# WIFI_Module.net
KiCad netlist of a schematic drawn in Altium Designer
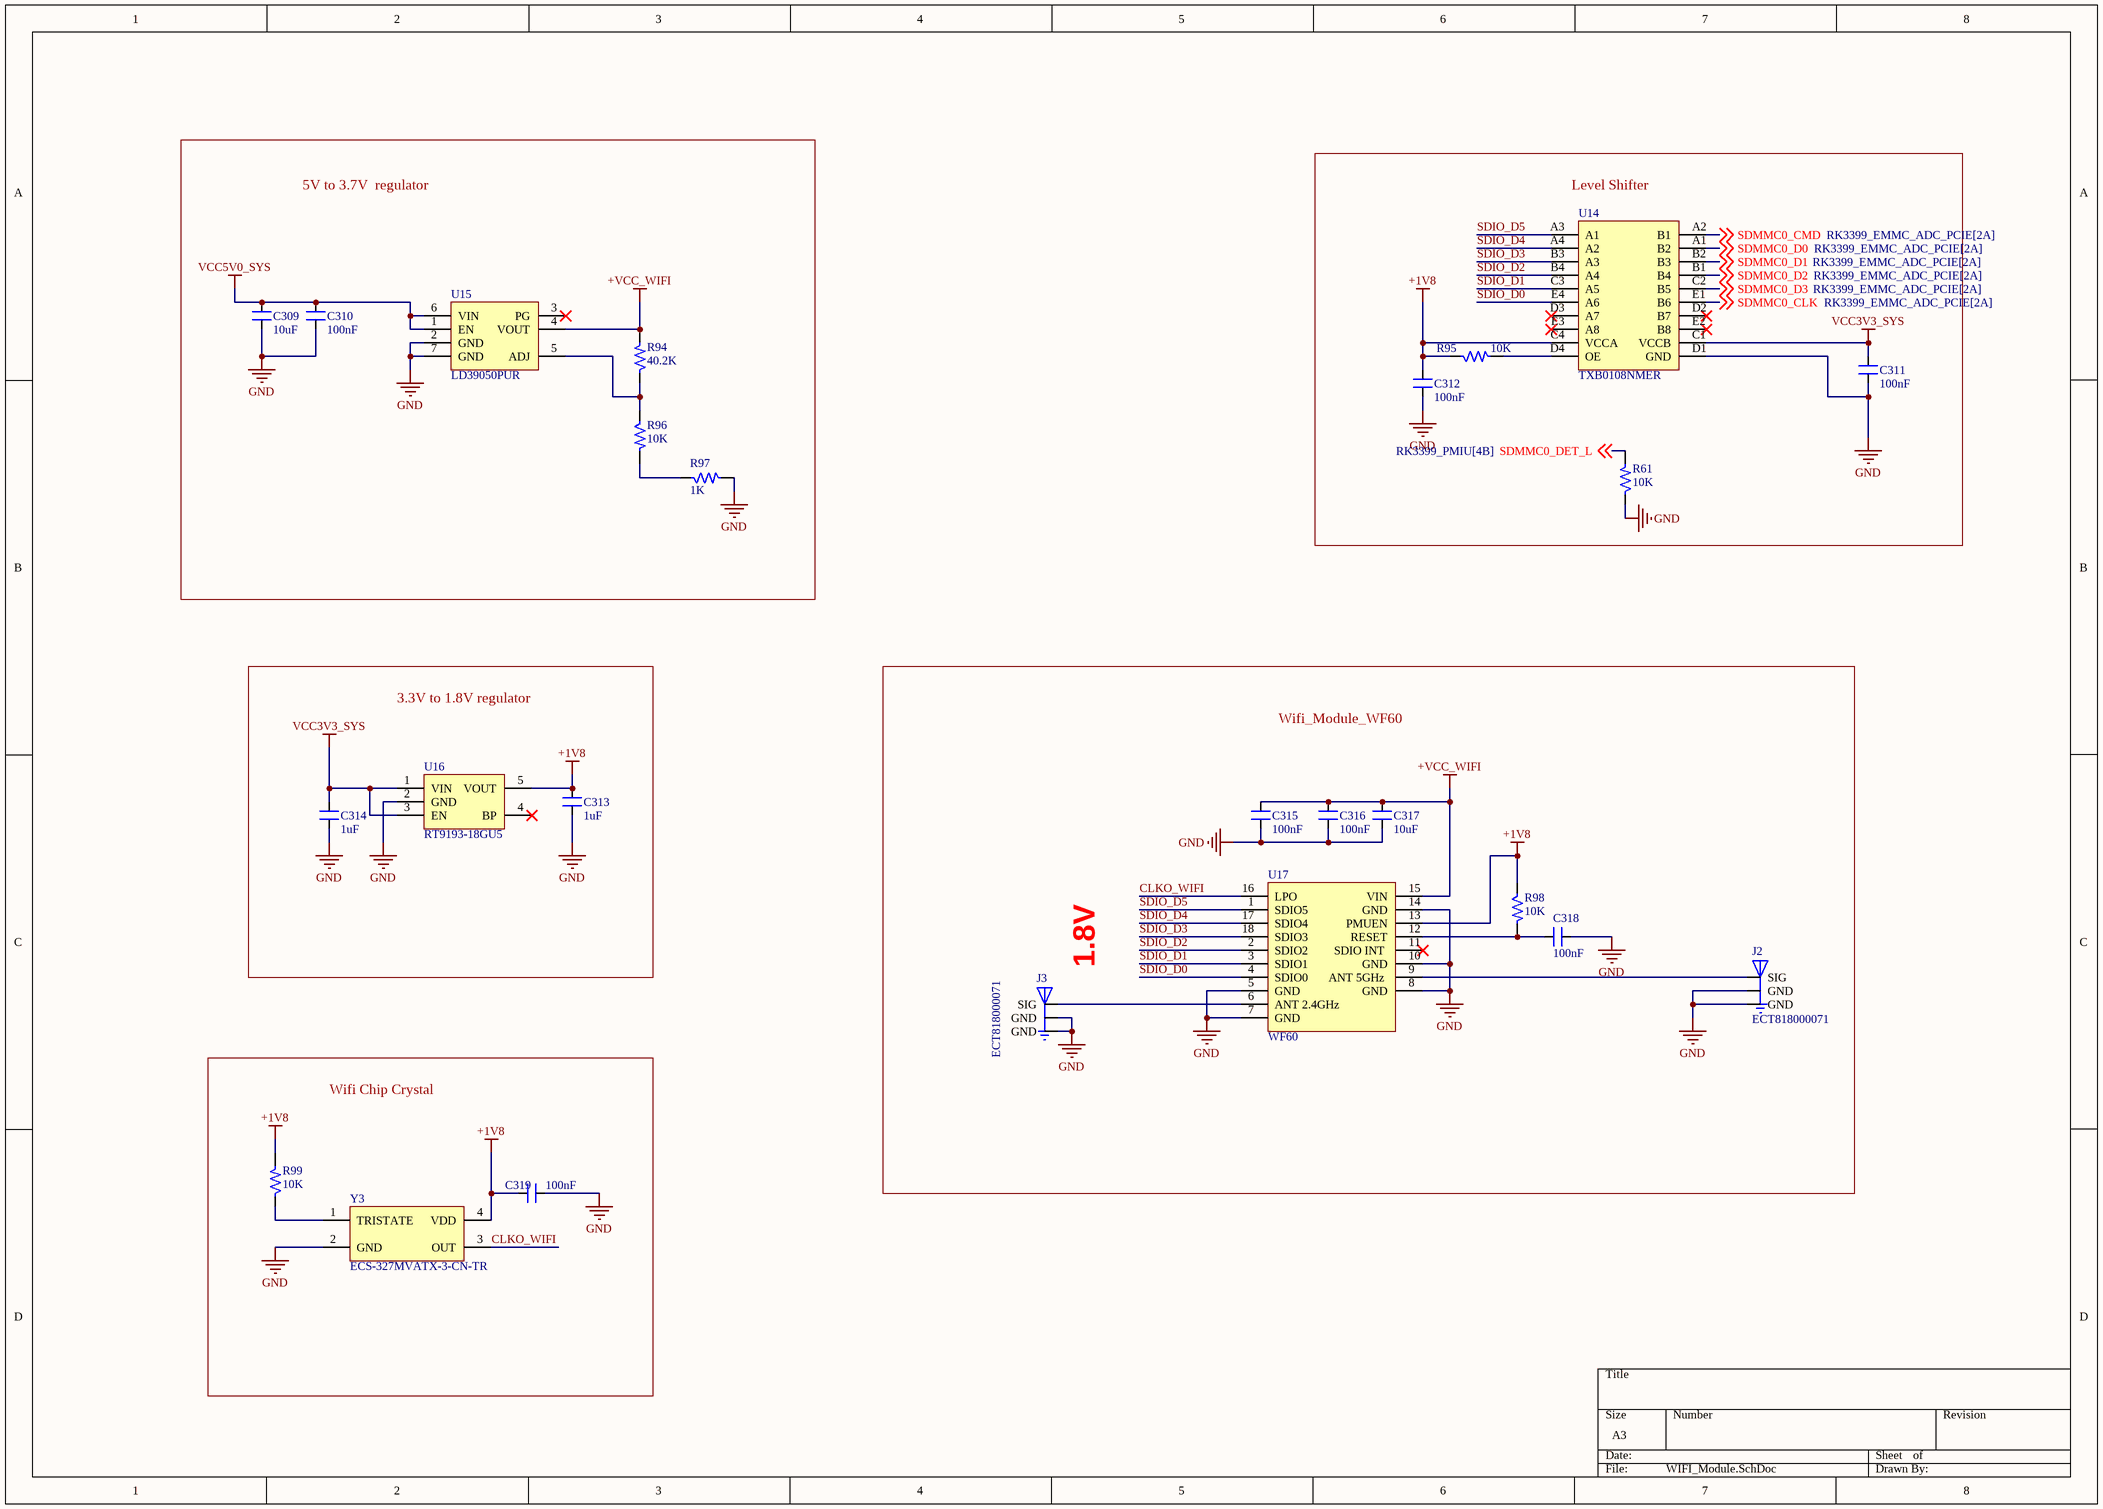
[diagram p0: WIFI_Module.SchDoc]

(export (version "E")
  (design (tool "Eeschema 10.0.6"))
  (components
    (comp (ref "C309")
      (value "10uF")
      (footprint "CAP_0603")
      (description "10µF ±10% 10V Ceramic Capacitor X5R 0603 (1608 Metric)")
      (fields
        (field (name "MANUFACTURER PART NUMBER") "GRM188R61A106KE69J")
        (field (name "MANUFACTURER") "Murata Electronics")
      )
      (libsource (lib "EsteemPCB_SOM_Course_schlib") (part "CAP_10uF-10V-10%-0603"))
    )
    (comp (ref "C310")
      (value "100nF")
      (footprint "CAP_0201")
      (description "0.1µF ±10% 25V Ceramic Capacitor X5R 0201 (0603 Metric)")
      (fields
        (field (name "MANUFACTURER") "TDK Corporation")
        (field (name "MANUFACTURER PART NUMBER") "C0603X5R1E104K030BB")
      )
      (libsource (lib "EsteemPCB_SOM_Course_schlib") (part "CAP_100nF-25V-10%-0201"))
    )
    (comp (ref "C311")
      (value "100nF")
      (footprint "CAP_0201")
      (description "0.1µF ±10% 25V Ceramic Capacitor X5R 0201 (0603 Metric)")
      (fields
        (field (name "MANUFACTURER") "TDK Corporation")
        (field (name "MANUFACTURER PART NUMBER") "C0603X5R1E104K030BB")
      )
      (libsource (lib "EsteemPCB_SOM_Course_schlib") (part "CAP_100nF-25V-10%-0201"))
    )
    (comp (ref "C312")
      (value "100nF")
      (footprint "CAP_0201")
      (description "0.1µF ±10% 25V Ceramic Capacitor X5R 0201 (0603 Metric)")
      (fields
        (field (name "MANUFACTURER") "TDK Corporation")
        (field (name "MANUFACTURER PART NUMBER") "C0603X5R1E104K030BB")
      )
      (libsource (lib "EsteemPCB_SOM_Course_schlib") (part "CAP_100nF-25V-10%-0201"))
    )
    (comp (ref "C313")
      (value "1uF")
      (footprint "CAP_0201")
      (description "1µF ±20% 16V Ceramic Capacitor X5R 0201 (0603 Metric)")
      (fields
        (field (name "MANUFACTURER") "Samsung Electro-Mechanics")
        (field (name "MANUFACTURER PART NUMBER") "CL03A105MO3NRNH")
      )
      (libsource (lib "EsteemPCB_SOM_Course_schlib") (part "CAP_1uF-16V-10%-0201"))
    )
    (comp (ref "C314")
      (value "1uF")
      (footprint "CAP_0201")
      (description "1µF ±20% 16V Ceramic Capacitor X5R 0201 (0603 Metric)")
      (fields
        (field (name "MANUFACTURER") "Samsung Electro-Mechanics")
        (field (name "MANUFACTURER PART NUMBER") "CL03A105MO3NRNH")
      )
      (libsource (lib "EsteemPCB_SOM_Course_schlib") (part "CAP_1uF-16V-10%-0201"))
    )
    (comp (ref "C315")
      (value "100nF")
      (footprint "CAP_0201")
      (description "0.1µF ±10% 25V Ceramic Capacitor X5R 0201 (0603 Metric)")
      (fields
        (field (name "MANUFACTURER") "TDK Corporation")
        (field (name "MANUFACTURER PART NUMBER") "C0603X5R1E104K030BB")
      )
      (libsource (lib "EsteemPCB_SOM_Course_schlib") (part "CAP_100nF-25V-10%-0201"))
    )
    (comp (ref "C316")
      (value "100nF")
      (footprint "CAP_0201")
      (description "0.1µF ±10% 25V Ceramic Capacitor X5R 0201 (0603 Metric)")
      (fields
        (field (name "MANUFACTURER") "TDK Corporation")
        (field (name "MANUFACTURER PART NUMBER") "C0603X5R1E104K030BB")
      )
      (libsource (lib "EsteemPCB_SOM_Course_schlib") (part "CAP_100nF-25V-10%-0201"))
    )
    (comp (ref "C317")
      (value "10uF")
      (footprint "CAP_0603")
      (description "10µF ±10% 10V Ceramic Capacitor X5R 0603 (1608 Metric)")
      (fields
        (field (name "MANUFACTURER PART NUMBER") "GRM188R61A106KE69J")
        (field (name "MANUFACTURER") "Murata Electronics")
      )
      (libsource (lib "EsteemPCB_SOM_Course_schlib") (part "CAP_10uF-10V-10%-0603"))
    )
    (comp (ref "C318")
      (value "100nF")
      (footprint "CAP_0201")
      (description "0.1µF ±10% 25V Ceramic Capacitor X5R 0201 (0603 Metric)")
      (fields
        (field (name "MANUFACTURER") "TDK Corporation")
        (field (name "MANUFACTURER PART NUMBER") "C0603X5R1E104K030BB")
      )
      (libsource (lib "EsteemPCB_SOM_Course_schlib") (part "CAP_100nF-25V-10%-0201"))
    )
    (comp (ref "C319")
      (value "100nF")
      (footprint "CAP_0201")
      (description "0.1µF ±10% 25V Ceramic Capacitor X5R 0201 (0603 Metric)")
      (fields
        (field (name "MANUFACTURER") "TDK Corporation")
        (field (name "MANUFACTURER PART NUMBER") "C0603X5R1E104K030BB")
      )
      (libsource (lib "EsteemPCB_SOM_Course_schlib") (part "CAP_100nF-25V-10%-0201"))
    )
    (comp (ref "J2")
      (value "ECT818000071")
      (footprint "CON3_UFL_116_SMD_ST")
      (description "SMD RF Connectors/Coaxial Connectors RoHS")
      (fields (field (name "MANUFACTURER") "ECT"))
      (libsource (lib "EsteemPCB_SOM_Course_schlib") (part "CON-PLG_3X1-ECT818000071-ST-SMD"))
    )
    (comp (ref "J3")
      (value "ECT818000071")
      (footprint "CON3_UFL_116_SMD_ST")
      (description "SMD RF Connectors/Coaxial Connectors RoHS")
      (fields (field (name "MANUFACTURER") "ECT"))
      (libsource (lib "EsteemPCB_SOM_Course_schlib") (part "CON-PLG_3X1-ECT818000071-ST-SMD"))
    )
    (comp (ref "R61")
      (value "10K")
      (footprint "RES_0201")
      (description "10 kOhms ±1% 0.05W, 1/20W Chip Resistor 0201 (0603 Metric) Thick Film")
      (fields
        (field (name "MANUFACTURER") "Stackpole Electronics Inc")
        (field (name "MANUFACTURER PART NUMBER") "RMCF0201FT10K0")
      )
      (libsource (lib "EsteemPCB_SOM_Course_schlib") (part "RES_10K-0.05W-1%-0201"))
    )
    (comp (ref "R94")
      (value "40.2K")
      (footprint "RES_0201")
      (fields
        (field (name "MANUFACTURER") "Yageo")
        (field (name "MANUFACTURER PART NUMBER") "AC0201FR-0740K2L")
      )
      (libsource (lib "EsteemPCB_SOM_Course_schlib") (part "RES_40.2K-0.05W-1%-0201"))
    )
    (comp (ref "R95")
      (value "10K")
      (footprint "RES_0201")
      (description "10 kOhms ±1% 0.05W, 1/20W Chip Resistor 0201 (0603 Metric) Thick Film")
      (fields
        (field (name "MANUFACTURER") "Stackpole Electronics Inc")
        (field (name "MANUFACTURER PART NUMBER") "RMCF0201FT10K0")
      )
      (libsource (lib "EsteemPCB_SOM_Course_schlib") (part "RES_10K-0.05W-1%-0201"))
    )
    (comp (ref "R96")
      (value "10K")
      (footprint "RES_0201")
      (description "10 kOhms ±1% 0.05W, 1/20W Chip Resistor 0201 (0603 Metric) Thick Film")
      (fields
        (field (name "MANUFACTURER") "Stackpole Electronics Inc")
        (field (name "MANUFACTURER PART NUMBER") "RMCF0201FT10K0")
      )
      (libsource (lib "EsteemPCB_SOM_Course_schlib") (part "RES_10K-0.05W-1%-0201"))
    )
    (comp (ref "R97")
      (value "1K")
      (footprint "RES_0201")
      (description "1 kOhms ±1% 0.05W, 1/20W Chip Resistor 0201 (0603 Metric) Thick Film")
      (fields
        (field (name "MANUFACTURER") "Yageo")
        (field (name "MANUFACTURER PART NUMBER") "RC0201FR-071KL")
      )
      (libsource (lib "EsteemPCB_SOM_Course_schlib") (part "RES_1K-0.05W-1%-0201"))
    )
    (comp (ref "R98")
      (value "10K")
      (footprint "RES_0201")
      (description "10 kOhms ±1% 0.05W, 1/20W Chip Resistor 0201 (0603 Metric) Thick Film")
      (fields
        (field (name "MANUFACTURER") "Stackpole Electronics Inc")
        (field (name "MANUFACTURER PART NUMBER") "RMCF0201FT10K0")
      )
      (libsource (lib "EsteemPCB_SOM_Course_schlib") (part "RES_10K-0.05W-1%-0201"))
    )
    (comp (ref "R99")
      (value "10K")
      (footprint "RES_0201")
      (description "10 kOhms ±1% 0.05W, 1/20W Chip Resistor 0201 (0603 Metric) Thick Film")
      (fields
        (field (name "MANUFACTURER") "Stackpole Electronics Inc")
        (field (name "MANUFACTURER PART NUMBER") "RMCF0201FT10K0")
      )
      (libsource (lib "EsteemPCB_SOM_Course_schlib") (part "RES_10K-0.05W-1%-0201"))
    )
    (comp (ref "U14")
      (value "TXB0108NMER")
      (footprint "NFBGA_31.4_125.9X102.36")
      (fields (field (name "MANUFACTURER") "Texas Instruments"))
      (libsource (lib "EsteemPCB_SOM_Course_schlib") (part "IC_TXB0108NMER"))
    )
    (comp (ref "U15")
      (value "LD39050PUR")
      (footprint "DFN-6_37.4_165_33X15_SMD")
      (description "Adjustable 5.5V 0.8V 500mA DFN-6 Linear Voltage Regulators RoHS")
      (fields (field (name "MANUFACTURER") "STMicroelectronics"))
      (libsource (lib "EsteemPCB_SOM_Course_schlib") (part "REG_5.5V-0~5.1V-0.5A-2.55W-DFN-6"))
    )
    (comp (ref "U16")
      (value "RT9193-18GU5")
      (footprint "SC70-5")
      (description "Linear Voltage Regulator IC 1 Output 300mA SC-70-5")
      (fields (field (name "MANUFACTURER") "Richtek USA Inc."))
      (libsource (lib "EsteemPCB_SOM_Course_schlib") (part "REG_1.8V-300mA-5.5V-SC70-5"))
    )
    (comp (ref "U17")
      (value "WF60")
      (footprint "MOD_WF60")
      (description "Amp’ed RF Tech presents the WF60 WiFi dual\r\nband module: 802.11abgn.")
      (fields (field (name "MANUFACTURER") "Amp’ed"))
      (libsource (lib "EsteemPCB_SOM_Course_schlib") (part "MOD_WF60-SMD"))
    )
    (comp (ref "Y3")
      (value "ECS-327MVATX-3-CN-TR")
      (footprint "XTAL_57_35X31_SMD")
      (description "32.768kHz XO (Standard) CMOS Oscillator 1.6V ~ 3.6V Enable/Disable 4-SMD, No Lead")
      (fields (field (name "MANUFACTURER") "ECS INC"))
      (libsource (lib "EsteemPCB_SOM_Course_schlib") (part "XTAL_ECS-327MVATX-2-CN-TR"))
    )
  )
  (nets
    (net (code "1") (name "+1V8") (class "Default")
      (node (ref "C312") (pin "1") (pinfunction "1_1") (pintype "passive"))
      (node (ref "C313") (pin "2") (pinfunction "2_2") (pintype "passive"))
      (node (ref "C319") (pin "1") (pinfunction "1_1") (pintype "passive"))
      (node (ref "R95") (pin "1") (pinfunction "1_1") (pintype "passive"))
      (node (ref "R98") (pin "1") (pinfunction "1_1") (pintype "passive"))
      (node (ref "R99") (pin "2") (pinfunction "2_2") (pintype "passive"))
      (node (ref "U14") (pin "C4") (pinfunction "VCCA_C4") (pintype "passive"))
      (node (ref "U16") (pin "5") (pinfunction "VOUT_5") (pintype "passive"))
      (node (ref "U17") (pin "13") (pinfunction "PMUEN_13") (pintype "passive"))
      (node (ref "Y3") (pin "4") (pinfunction "VDD_4") (pintype "passive"))
    )
    (net (code "2") (name "+VCC_WIFI") (class "Default")
      (node (ref "C315") (pin "1") (pinfunction "1_1") (pintype "passive"))
      (node (ref "C316") (pin "1") (pinfunction "1_1") (pintype "passive"))
      (node (ref "C317") (pin "2") (pinfunction "2_2") (pintype "passive"))
      (node (ref "R94") (pin "2") (pinfunction "2_2") (pintype "passive"))
      (node (ref "U15") (pin "4") (pinfunction "VOUT_4") (pintype "passive"))
      (node (ref "U17") (pin "15") (pinfunction "VIN_15") (pintype "passive"))
    )
    (net (code "3") (name "/CLKO_WIFI") (class "Default")
      (node (ref "U17") (pin "16") (pinfunction "LPO_16") (pintype "passive"))
      (node (ref "Y3") (pin "3") (pinfunction "OUT_3") (pintype "passive"))
    )
    (net (code "4") (name "/SDIO_D0") (class "Default")
      (node (ref "U14") (pin "E4") (pinfunction "A6_E4") (pintype "passive"))
      (node (ref "U17") (pin "4") (pinfunction "SDIO0_4") (pintype "passive"))
    )
    (net (code "5") (name "/SDIO_D1") (class "Default")
      (node (ref "U14") (pin "C3") (pinfunction "A5_C3") (pintype "passive"))
      (node (ref "U17") (pin "3") (pinfunction "SDIO1_3") (pintype "passive"))
    )
    (net (code "6") (name "/SDIO_D2") (class "Default")
      (node (ref "U14") (pin "B4") (pinfunction "A4_B4") (pintype "passive"))
      (node (ref "U17") (pin "2") (pinfunction "SDIO2_2") (pintype "passive"))
    )
    (net (code "7") (name "/SDIO_D3") (class "Default")
      (node (ref "U14") (pin "B3") (pinfunction "A3_B3") (pintype "passive"))
      (node (ref "U17") (pin "18") (pinfunction "SDIO3_18") (pintype "passive"))
    )
    (net (code "8") (name "/SDIO_D4") (class "Default")
      (node (ref "U14") (pin "A4") (pinfunction "A2_A4") (pintype "passive"))
      (node (ref "U17") (pin "17") (pinfunction "SDIO4_17") (pintype "passive"))
    )
    (net (code "9") (name "/SDIO_D5") (class "Default")
      (node (ref "U14") (pin "A3") (pinfunction "A1_A3") (pintype "passive"))
      (node (ref "U17") (pin "1") (pinfunction "SDIO5_1") (pintype "passive"))
    )
    (net (code "10") (name "GND") (class "Default")
      (node (ref "C309") (pin "1") (pinfunction "1_1") (pintype "passive"))
      (node (ref "C310") (pin "2") (pinfunction "2_2") (pintype "passive"))
      (node (ref "C311") (pin "2") (pinfunction "2_2") (pintype "passive"))
      (node (ref "C312") (pin "2") (pinfunction "2_2") (pintype "passive"))
      (node (ref "C313") (pin "1") (pinfunction "1_1") (pintype "passive"))
      (node (ref "C314") (pin "1") (pinfunction "1_1") (pintype "passive"))
      (node (ref "C315") (pin "2") (pinfunction "2_2") (pintype "passive"))
      (node (ref "C316") (pin "2") (pinfunction "2_2") (pintype "passive"))
      (node (ref "C317") (pin "1") (pinfunction "1_1") (pintype "passive"))
      (node (ref "C318") (pin "2") (pinfunction "2_2") (pintype "passive"))
      (node (ref "C319") (pin "2") (pinfunction "2_2") (pintype "passive"))
      (node (ref "J2") (pin "1") (pinfunction "GND_1") (pintype "passive"))
      (node (ref "J2") (pin "3") (pinfunction "GND_3") (pintype "passive"))
      (node (ref "J3") (pin "1") (pinfunction "GND_1") (pintype "passive"))
      (node (ref "J3") (pin "3") (pinfunction "GND_3") (pintype "passive"))
      (node (ref "R61") (pin "1") (pinfunction "1_1") (pintype "passive"))
      (node (ref "R97") (pin "2") (pinfunction "2_2") (pintype "passive"))
      (node (ref "U14") (pin "D1") (pinfunction "GND_D1") (pintype "passive"))
      (node (ref "U15") (pin "2") (pinfunction "GND_2") (pintype "passive"))
      (node (ref "U15") (pin "7") (pinfunction "GND_7") (pintype "passive"))
      (node (ref "U16") (pin "2") (pinfunction "GND_2") (pintype "passive"))
      (node (ref "U17") (pin "10") (pinfunction "GND_10") (pintype "passive"))
      (node (ref "U17") (pin "14") (pinfunction "GND_14") (pintype "passive"))
      (node (ref "U17") (pin "5") (pinfunction "GND_5") (pintype "passive"))
      (node (ref "U17") (pin "7") (pinfunction "GND_7") (pintype "passive"))
      (node (ref "U17") (pin "8") (pinfunction "GND_8") (pintype "passive"))
      (node (ref "Y3") (pin "2") (pinfunction "GND_2") (pintype "passive"))
    )
    (net (code "11") (name "Net-(J2-SIG)") (class "Default")
      (node (ref "J2") (pin "2") (pinfunction "SIG_2") (pintype "passive"))
      (node (ref "U17") (pin "9") (pinfunction "ANT_5GHz_9") (pintype "passive"))
    )
    (net (code "12") (name "Net-(J3-SIG)") (class "Default")
      (node (ref "J3") (pin "2") (pinfunction "SIG_2") (pintype "passive"))
      (node (ref "U17") (pin "6") (pinfunction "ANT_2.4GHz_6") (pintype "passive"))
    )
    (net (code "13") (name "Net-(R96-Pad2)") (class "Default")
      (node (ref "R96") (pin "2") (pinfunction "2_2") (pintype "passive"))
      (node (ref "R97") (pin "1") (pinfunction "1_1") (pintype "passive"))
    )
    (net (code "14") (name "Net-(U14-OE)") (class "Default")
      (node (ref "R95") (pin "2") (pinfunction "2_2") (pintype "passive"))
      (node (ref "U14") (pin "D4") (pinfunction "OE_D4") (pintype "passive"))
    )
    (net (code "15") (name "Net-(U15-ADJ)") (class "Default")
      (node (ref "R94") (pin "1") (pinfunction "1_1") (pintype "passive"))
      (node (ref "R96") (pin "1") (pinfunction "1_1") (pintype "passive"))
      (node (ref "U15") (pin "5") (pinfunction "ADJ_5") (pintype "passive"))
    )
    (net (code "16") (name "Net-(U17-RESET)") (class "Default")
      (node (ref "C318") (pin "1") (pinfunction "1_1") (pintype "passive"))
      (node (ref "R98") (pin "2") (pinfunction "2_2") (pintype "passive"))
      (node (ref "U17") (pin "12") (pinfunction "RESET_12") (pintype "passive"))
    )
    (net (code "17") (name "Net-(Y3-TRISTATE)") (class "Default")
      (node (ref "R99") (pin "1") (pinfunction "1_1") (pintype "passive"))
      (node (ref "Y3") (pin "1") (pinfunction "TRISTATE_1") (pintype "passive"))
    )
    (net (code "18") (name "SDMMC0_CLK") (class "Default")
      (node (ref "U14") (pin "E1") (pinfunction "B6_E1") (pintype "passive"))
    )
    (net (code "19") (name "SDMMC0_CMD") (class "Default")
      (node (ref "U14") (pin "A2") (pinfunction "B1_A2") (pintype "passive"))
    )
    (net (code "20") (name "SDMMC0_D0") (class "Default")
      (node (ref "U14") (pin "A1") (pinfunction "B2_A1") (pintype "passive"))
    )
    (net (code "21") (name "SDMMC0_D1") (class "Default")
      (node (ref "U14") (pin "B2") (pinfunction "B3_B2") (pintype "passive"))
    )
    (net (code "22") (name "SDMMC0_D2") (class "Default")
      (node (ref "U14") (pin "B1") (pinfunction "B4_B1") (pintype "passive"))
    )
    (net (code "23") (name "SDMMC0_D3") (class "Default")
      (node (ref "U14") (pin "C2") (pinfunction "B5_C2") (pintype "passive"))
    )
    (net (code "24") (name "SDMMC0_DET_L") (class "Default")
      (node (ref "R61") (pin "2") (pinfunction "2_2") (pintype "passive"))
    )
    (net (code "25") (name "VCC3V3_SYS") (class "Default")
      (node (ref "C311") (pin "1") (pinfunction "1_1") (pintype "passive"))
      (node (ref "C314") (pin "2") (pinfunction "2_2") (pintype "passive"))
      (node (ref "U14") (pin "C1") (pinfunction "VCCB_C1") (pintype "passive"))
      (node (ref "U16") (pin "1") (pinfunction "VIN_1") (pintype "passive"))
      (node (ref "U16") (pin "3") (pinfunction "EN_3") (pintype "passive"))
    )
    (net (code "26") (name "VCC5V0_SYS") (class "Default")
      (node (ref "C309") (pin "2") (pinfunction "2_2") (pintype "passive"))
      (node (ref "C310") (pin "1") (pinfunction "1_1") (pintype "passive"))
      (node (ref "U15") (pin "1") (pinfunction "EN_1") (pintype "passive"))
      (node (ref "U15") (pin "6") (pinfunction "VIN_6") (pintype "passive"))
    )
    (net (code "27") (name "unconnected-(U14-A7-PadD3)") (class "Default")
      (node (ref "U14") (pin "D3") (pinfunction "A7_D3") (pintype "passive+no_connect"))
    )
    (net (code "28") (name "unconnected-(U14-A8-PadE3)") (class "Default")
      (node (ref "U14") (pin "E3") (pinfunction "A8_E3") (pintype "passive+no_connect"))
    )
    (net (code "29") (name "unconnected-(U14-B7-PadD2)") (class "Default")
      (node (ref "U14") (pin "D2") (pinfunction "B7_D2") (pintype "passive+no_connect"))
    )
    (net (code "30") (name "unconnected-(U14-B8-PadE2)") (class "Default")
      (node (ref "U14") (pin "E2") (pinfunction "B8_E2") (pintype "passive+no_connect"))
    )
    (net (code "31") (name "unconnected-(U15-PG-Pad3)") (class "Default")
      (node (ref "U15") (pin "3") (pinfunction "PG_3") (pintype "passive+no_connect"))
    )
    (net (code "32") (name "unconnected-(U16-BP-Pad4)") (class "Default")
      (node (ref "U16") (pin "4") (pinfunction "BP_4") (pintype "passive+no_connect"))
    )
    (net (code "33") (name "unconnected-(U17-SDIO_INT-Pad11)") (class "Default")
      (node (ref "U17") (pin "11") (pinfunction "SDIO_INT_11") (pintype "passive+no_connect"))
    )
  )
)
